# window-sensor.net
KiCad netlist of a schematic drawn in EAGLE
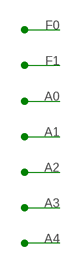
[diagram p0: schematic, sheet 1]
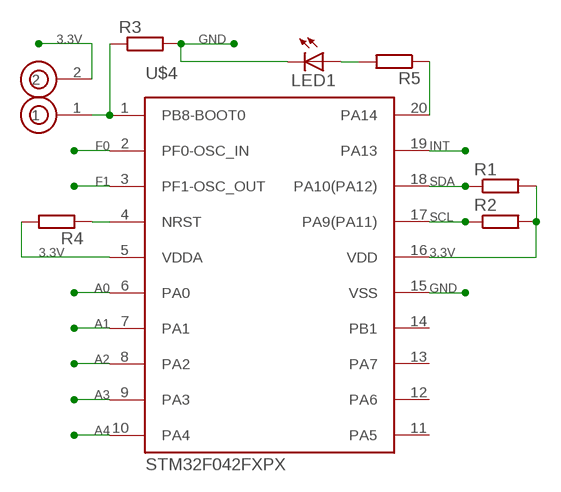
[diagram p1: schematic, sheet 2]
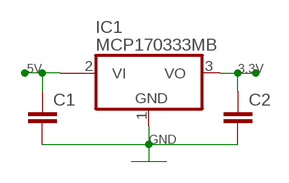
[diagram p2: schematic, sheet 3]
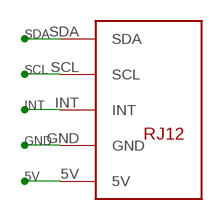
[diagram p3: schematic, sheet 4]

(export (version "E")
  (design (tool "Eeschema 10.0.6"))
  (components
    (comp (ref "U$2")
      (value "RJ12SMD")
      (footprint "eagle-import:RJ12_SMD")
      (libsource (lib "eagle-import") (part "RJ12SMD"))
    )
    (comp (ref "C1")
      (value "C-EUC1206")
      (footprint "eagle-import:C1206")
      (libsource (lib "eagle-import") (part "C-EUC1206"))
    )
    (comp (ref "C2")
      (value "C-EUC1206")
      (footprint "eagle-import:C1206")
      (libsource (lib "eagle-import") (part "C-EUC1206"))
    )
    (comp (ref "IC1")
      (value "MCP170333MB")
      (footprint "eagle-import:SOT89")
      (libsource (lib "eagle-import") (part "MCP1703MB33"))
    )
    (comp (ref "LED1")
      (value "LEDSML1206")
      (footprint "eagle-import:SML1206")
      (libsource (lib "eagle-import") (part "LEDSML1206"))
    )
    (comp (ref "R1")
      (value "R-EU_R1206")
      (footprint "eagle-import:R1206")
      (libsource (lib "eagle-import") (part "R-EU_R1206"))
    )
    (comp (ref "R2")
      (value "R-EU_R0603")
      (footprint "eagle-import:R0603")
      (libsource (lib "eagle-import") (part "R-EU_R0603"))
    )
    (comp (ref "R3")
      (value "R-EU_R1206")
      (footprint "eagle-import:R1206")
      (libsource (lib "eagle-import") (part "R-EU_R1206"))
    )
    (comp (ref "R4")
      (value "R-EU_R0603")
      (footprint "eagle-import:R0603")
      (libsource (lib "eagle-import") (part "R-EU_R0603"))
    )
    (comp (ref "R5")
      (value "R-EU_R0603")
      (footprint "eagle-import:R0603")
      (libsource (lib "eagle-import") (part "R-EU_R0603"))
    )
    (comp (ref "U$3")
      (value "GOLDPIN_2")
      (footprint "eagle-import:GOLDPIN_2_SMD")
      (libsource (lib "eagle-import") (part "GOLDPIN_2"))
    )
    (comp (ref "U$4")
      (value "STM32F042FXPX")
      (footprint "eagle-import:TSSOP20")
      (libsource (lib "eagle-import") (part "STM32F042FXPX"))
    )
  )
  (nets
    (net (code "1") (name "3.3V") (class "Default")
      (node (ref "C2") (pin "1") (pinfunction "1_1") (pintype "passive"))
      (node (ref "IC1") (pin "3") (pinfunction "VO_3") (pintype "passive"))
      (node (ref "R1") (pin "2") (pinfunction "2_2") (pintype "passive"))
      (node (ref "R2") (pin "2") (pinfunction "2_2") (pintype "passive"))
      (node (ref "R4") (pin "2") (pinfunction "2_2") (pintype "passive"))
      (node (ref "U$3") (pin "2") (pinfunction "2_2") (pintype "bidirectional"))
      (node (ref "U$4") (pin "16") (pinfunction "VDD_16") (pintype "bidirectional"))
      (node (ref "U$4") (pin "5") (pinfunction "VDDA_5") (pintype "bidirectional"))
    )
    (net (code "2") (name "5V") (class "Default")
      (node (ref "C1") (pin "1") (pinfunction "1_1") (pintype "passive"))
      (node (ref "IC1") (pin "2@1") (pinfunction "VI1_2@1") (pintype "input"))
      (node (ref "U$2") (pin "5V") (pinfunction "5V_5V") (pintype "bidirectional"))
    )
    (net (code "3") (name "A0") (class "Default")
      (node (ref "U$4") (pin "6") (pinfunction "PA0_6") (pintype "bidirectional"))
    )
    (net (code "4") (name "A1") (class "Default")
      (node (ref "U$4") (pin "7") (pinfunction "PA1_7") (pintype "bidirectional"))
    )
    (net (code "5") (name "A2") (class "Default")
      (node (ref "U$4") (pin "8") (pinfunction "PA2_8") (pintype "bidirectional"))
    )
    (net (code "6") (name "A3") (class "Default")
      (node (ref "U$4") (pin "9") (pinfunction "PA3_9") (pintype "bidirectional"))
    )
    (net (code "7") (name "A4") (class "Default")
      (node (ref "U$4") (pin "10") (pinfunction "PA4_10") (pintype "bidirectional"))
    )
    (net (code "8") (name "F0") (class "Default")
      (node (ref "U$4") (pin "2") (pinfunction "PF0-OSC_IN_2") (pintype "bidirectional"))
    )
    (net (code "9") (name "F1") (class "Default")
      (node (ref "U$4") (pin "3") (pinfunction "PF1-OSC_OUT_3") (pintype "bidirectional"))
    )
    (net (code "10") (name "GND") (class "Default")
      (node (ref "C1") (pin "2") (pinfunction "2_2") (pintype "passive"))
      (node (ref "C2") (pin "2") (pinfunction "2_2") (pintype "passive"))
      (node (ref "IC1") (pin "1") (pinfunction "GND_1") (pintype "passive"))
      (node (ref "LED1") (pin "C") (pinfunction "C_C") (pintype "passive"))
      (node (ref "R3") (pin "2") (pinfunction "2_2") (pintype "passive"))
      (node (ref "U$2") (pin "GND") (pinfunction "GND_GND") (pintype "bidirectional"))
      (node (ref "U$4") (pin "15") (pinfunction "VSS_15") (pintype "bidirectional"))
    )
    (net (code "11") (name "INT") (class "Default")
      (node (ref "U$2") (pin "INT") (pinfunction "INT_INT") (pintype "bidirectional"))
      (node (ref "U$4") (pin "19") (pinfunction "PA13_19") (pintype "bidirectional"))
    )
    (net (code "12") (name "Net-(LED1-PadA)") (class "Default")
      (node (ref "LED1") (pin "A") (pinfunction "A_A") (pintype "passive"))
      (node (ref "R5") (pin "2") (pinfunction "2_2") (pintype "passive"))
    )
    (net (code "13") (name "Net-(U$4-NRST)") (class "Default")
      (node (ref "R4") (pin "1") (pinfunction "1_1") (pintype "passive"))
      (node (ref "U$4") (pin "4") (pinfunction "NRST_4") (pintype "bidirectional"))
    )
    (net (code "14") (name "Net-(U$4-PA14)") (class "Default")
      (node (ref "R5") (pin "1") (pinfunction "1_1") (pintype "passive"))
      (node (ref "U$4") (pin "20") (pinfunction "PA14_20") (pintype "bidirectional"))
    )
    (net (code "15") (name "Net-(U$4-PB8-BOOT0)") (class "Default")
      (node (ref "R3") (pin "1") (pinfunction "1_1") (pintype "passive"))
      (node (ref "U$3") (pin "1") (pinfunction "1_1") (pintype "bidirectional"))
      (node (ref "U$4") (pin "1") (pinfunction "PB8-BOOT0_1") (pintype "bidirectional"))
    )
    (net (code "16") (name "SCL") (class "Default")
      (node (ref "R2") (pin "1") (pinfunction "1_1") (pintype "passive"))
      (node (ref "U$2") (pin "SCL") (pinfunction "SCL_SCL") (pintype "bidirectional"))
      (node (ref "U$4") (pin "17") (pinfunction "PA9(PA11)_17") (pintype "bidirectional"))
    )
    (net (code "17") (name "SDA") (class "Default")
      (node (ref "R1") (pin "1") (pinfunction "1_1") (pintype "passive"))
      (node (ref "U$2") (pin "SDA") (pinfunction "SDA_SDA") (pintype "bidirectional"))
      (node (ref "U$4") (pin "18") (pinfunction "PA10(PA12)_18") (pintype "bidirectional"))
    )
    (net (code "18") (name "unconnected-(IC1-VI-Pad2)") (class "Default")
      (node (ref "IC1") (pin "2") (pinfunction "VI_2") (pintype "input"))
    )
    (net (code "19") (name "unconnected-(U$4-PA5-Pad11)") (class "Default")
      (node (ref "U$4") (pin "11") (pinfunction "PA5_11") (pintype "bidirectional"))
    )
    (net (code "20") (name "unconnected-(U$4-PA6-Pad12)") (class "Default")
      (node (ref "U$4") (pin "12") (pinfunction "PA6_12") (pintype "bidirectional"))
    )
    (net (code "21") (name "unconnected-(U$4-PA7-Pad13)") (class "Default")
      (node (ref "U$4") (pin "13") (pinfunction "PA7_13") (pintype "bidirectional"))
    )
    (net (code "22") (name "unconnected-(U$4-PB1-Pad14)") (class "Default")
      (node (ref "U$4") (pin "14") (pinfunction "PB1_14") (pintype "bidirectional"))
    )
  )
)
